# st-link-v2.net
KiCad netlist of a schematic drawn in Altium Designer
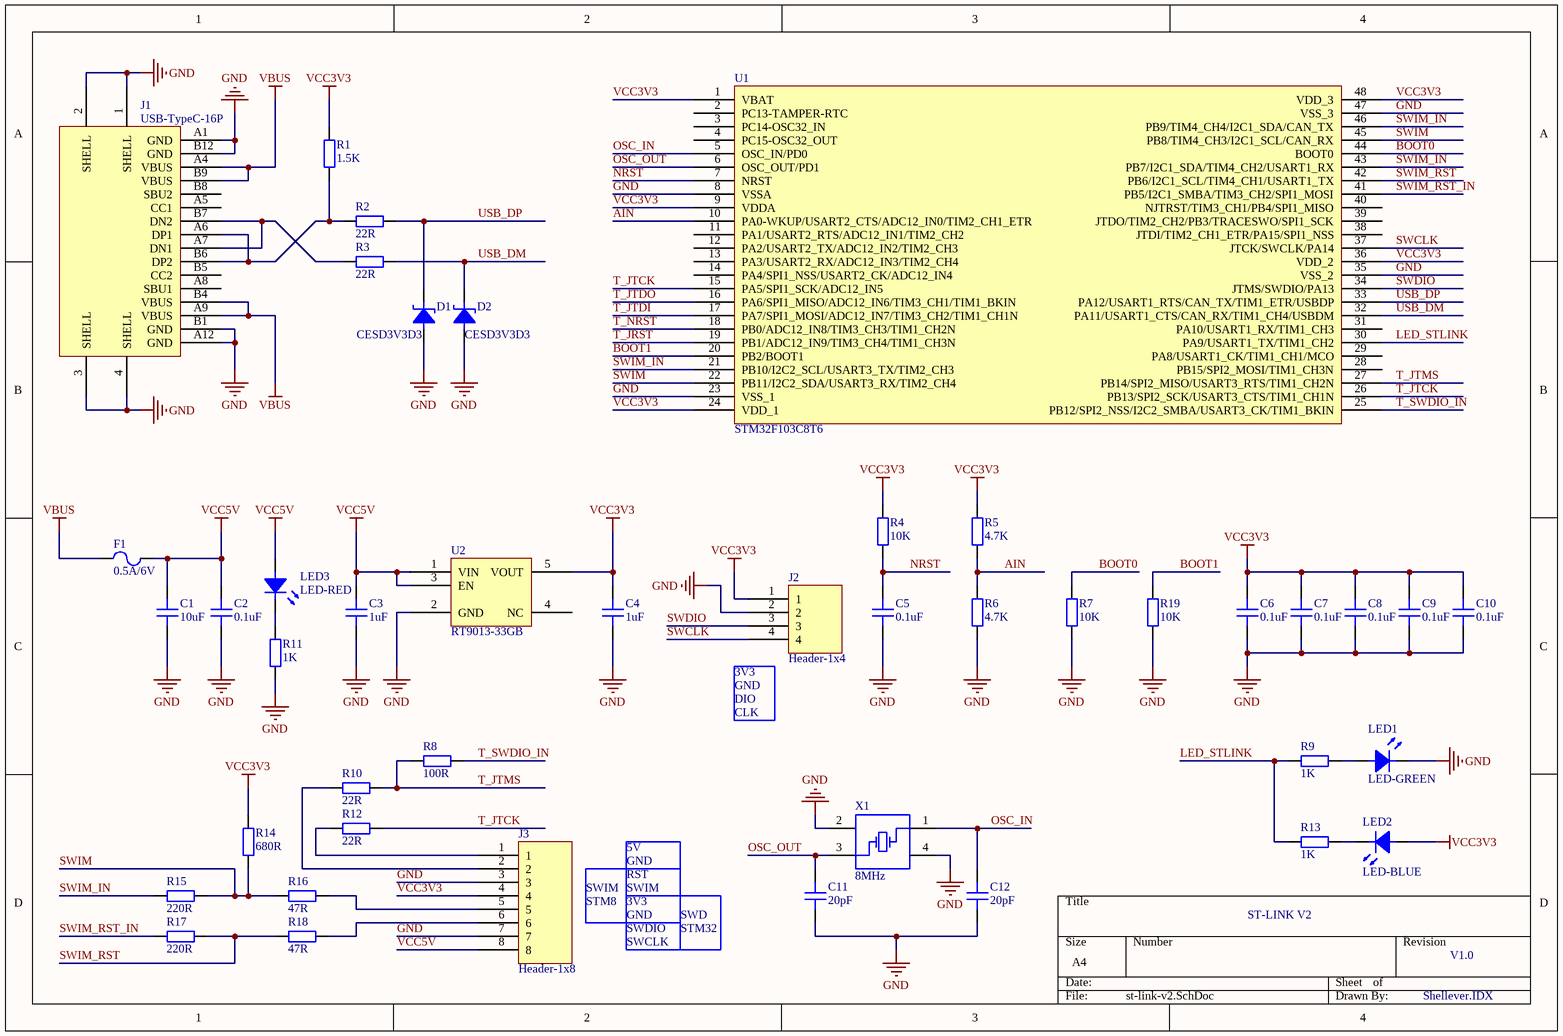
[diagram p0: st-link-v2.SchDoc]

(export (version "E")
  (design (tool "Eeschema 10.0.6"))
  (components
    (comp (ref "C1")
      (value "10uF")
      (footprint "0603C")
      (description "Capacitor")
      (libsource (lib "LinuxforSchLib") (part "CAP"))
    )
    (comp (ref "C2")
      (value "0.1uF")
      (footprint "0603C")
      (description "Capacitor")
      (libsource (lib "LinuxforSchLib") (part "CAP"))
    )
    (comp (ref "C3")
      (value "1uF")
      (footprint "0603C")
      (description "Capacitor")
      (libsource (lib "LinuxforSchLib") (part "CAP"))
    )
    (comp (ref "C4")
      (value "1uF")
      (footprint "0603C")
      (description "Capacitor")
      (libsource (lib "LinuxforSchLib") (part "CAP"))
    )
    (comp (ref "C5")
      (value "0.1uF")
      (footprint "0603C")
      (description "Capacitor")
      (libsource (lib "LinuxforSchLib") (part "CAP"))
    )
    (comp (ref "C6")
      (value "0.1uF")
      (footprint "0603C")
      (description "Capacitor")
      (libsource (lib "LinuxforSchLib") (part "CAP"))
    )
    (comp (ref "C7")
      (value "0.1uF")
      (footprint "0603C")
      (description "Capacitor")
      (libsource (lib "LinuxforSchLib") (part "CAP"))
    )
    (comp (ref "C8")
      (value "0.1uF")
      (footprint "0603C")
      (description "Capacitor")
      (libsource (lib "LinuxforSchLib") (part "CAP"))
    )
    (comp (ref "C9")
      (value "0.1uF")
      (footprint "0603C")
      (description "Capacitor")
      (libsource (lib "LinuxforSchLib") (part "CAP"))
    )
    (comp (ref "C10")
      (value "0.1uF")
      (footprint "0603C")
      (description "Capacitor")
      (libsource (lib "LinuxforSchLib") (part "CAP"))
    )
    (comp (ref "C11")
      (value "20pF")
      (footprint "0603C")
      (description "Capacitor")
      (libsource (lib "LinuxforSchLib") (part "CAP"))
    )
    (comp (ref "C12")
      (value "20pF")
      (footprint "0603C")
      (description "Capacitor")
      (libsource (lib "LinuxforSchLib") (part "CAP"))
    )
    (comp (ref "D1")
      (value "CESD3V3D3")
      (footprint "SOD-323_L1.8-W1.3-LS2.5-RD")
      (description "Uni-direction ESD Protection Diode")
      (libsource (lib "LinuxforSchLib") (part "CESD3V3D3"))
    )
    (comp (ref "D2")
      (value "CESD3V3D3")
      (footprint "SOD-323_L1.8-W1.3-LS2.5-RD")
      (description "Uni-direction ESD Protection Diode")
      (libsource (lib "LinuxforSchLib") (part "CESD3V3D3"))
    )
    (comp (ref "F1")
      (value "0.5A/6V")
      (footprint "0603F")
      (description "Fuse")
      (libsource (lib "LinuxforSchLib") (part "Fuse"))
    )
    (comp (ref "J1")
      (value "USB-TypeC-16P")
      (footprint "USB-C-SMD_KH-TYPE-C-16P")
      (description "USB Type C 16 Pin Female")
      (libsource (lib "LinuxforSchLib") (part "USB-TypeC-16P"))
    )
    (comp (ref "J2")
      (value "Header-1x4")
      (footprint "HDR-TH_4P-P2.54-V-M")
      (description "Header with 1x4 pins")
      (libsource (lib "LinuxforSchLib") (part "Header-1x4"))
    )
    (comp (ref "J3")
      (value "Header-1x8")
      (footprint "HDR-TH_8P-P2.54-V-M")
      (description "Header with 1x8 pins")
      (libsource (lib "LinuxforSchLib") (part "Header-1x8"))
    )
    (comp (ref "LED1")
      (value "LED-GREEN")
      (footprint "0603LED")
      (description "LED")
      (libsource (lib "LinuxforSchLib") (part "LED"))
    )
    (comp (ref "LED2")
      (value "LED-BLUE")
      (footprint "0603LED")
      (description "LED")
      (libsource (lib "LinuxforSchLib") (part "LED"))
    )
    (comp (ref "LED3")
      (value "LED-RED")
      (footprint "0603LED")
      (description "LED")
      (libsource (lib "") (part "LED_1"))
    )
    (comp (ref "R1")
      (value "1.5K")
      (footprint "0603R")
      (description "Resistor")
      (libsource (lib "LinuxforSchLib") (part "RES"))
    )
    (comp (ref "R2")
      (value "22R")
      (footprint "0603R")
      (description "Resistor")
      (libsource (lib "LinuxforSchLib") (part "RES"))
    )
    (comp (ref "R3")
      (value "22R")
      (footprint "0603R")
      (description "Resistor")
      (libsource (lib "LinuxforSchLib") (part "RES"))
    )
    (comp (ref "R4")
      (value "10K")
      (footprint "0603R")
      (description "Resistor")
      (libsource (lib "LinuxforSchLib") (part "RES"))
    )
    (comp (ref "R5")
      (value "4.7K")
      (footprint "0603R")
      (description "Resistor")
      (libsource (lib "LinuxforSchLib") (part "RES"))
    )
    (comp (ref "R6")
      (value "4.7K")
      (footprint "0603R")
      (description "Resistor")
      (libsource (lib "LinuxforSchLib") (part "RES"))
    )
    (comp (ref "R7")
      (value "10K")
      (footprint "0603R")
      (description "Resistor")
      (libsource (lib "LinuxforSchLib") (part "RES"))
    )
    (comp (ref "R8")
      (value "100R")
      (footprint "0603R")
      (description "Resistor")
      (libsource (lib "LinuxforSchLib") (part "RES"))
    )
    (comp (ref "R9")
      (value "1K")
      (footprint "0603R")
      (description "Resistor")
      (libsource (lib "LinuxforSchLib") (part "RES"))
    )
    (comp (ref "R10")
      (value "22R")
      (footprint "0603R")
      (description "Resistor")
      (libsource (lib "LinuxforSchLib") (part "RES"))
    )
    (comp (ref "R11")
      (value "1K")
      (footprint "0603R")
      (description "Resistor")
      (libsource (lib "LinuxforSchLib") (part "RES"))
    )
    (comp (ref "R12")
      (value "22R")
      (footprint "0603R")
      (description "Resistor")
      (libsource (lib "LinuxforSchLib") (part "RES"))
    )
    (comp (ref "R13")
      (value "1K")
      (footprint "0603R")
      (description "Resistor")
      (libsource (lib "LinuxforSchLib") (part "RES"))
    )
    (comp (ref "R14")
      (value "680R")
      (footprint "0603R")
      (description "Resistor")
      (libsource (lib "LinuxforSchLib") (part "RES"))
    )
    (comp (ref "R15")
      (value "220R")
      (footprint "0603R")
      (description "Resistor")
      (libsource (lib "LinuxforSchLib") (part "RES"))
    )
    (comp (ref "R16")
      (value "47R")
      (footprint "0603R")
      (description "Resistor")
      (libsource (lib "LinuxforSchLib") (part "RES"))
    )
    (comp (ref "R17")
      (value "220R")
      (footprint "0603R")
      (description "Resistor")
      (libsource (lib "LinuxforSchLib") (part "RES"))
    )
    (comp (ref "R18")
      (value "47R")
      (footprint "0603R")
      (description "Resistor")
      (libsource (lib "LinuxforSchLib") (part "RES"))
    )
    (comp (ref "R19")
      (value "10K")
      (footprint "0603R")
      (description "Resistor")
      (libsource (lib "LinuxforSchLib") (part "RES"))
    )
    (comp (ref "U1")
      (value "STM32F103C8T6")
      (footprint "LQFP-48_L7.0-W7.0-P0.50-LS9.0-BL")
      (description "STM32F103x8 LQFP48")
      (libsource (lib "LinuxforSchLib") (part "STM32F103x8_LQFP48"))
    )
    (comp (ref "U2")
      (value "RT9013-33GB")
      (footprint "SOT-23-5_L3.0-W1.7-P0.95-LS2.8-BR")
      (description "500mA LDO Regulator without Bypass Capacitor")
      (fields
        (field (name "MANUFACTURER") "RICHTEK<https://tw.richtek.com/>")
        (field (name "CONTRIBUTOR") "Shellever.IDX<shellever@163.com>")
      )
      (libsource (lib "LinuxforSchLib") (part "RT9013"))
    )
    (comp (ref "X1")
      (value "8MHz")
      (footprint "OSC-SMD_3225-4P-L3.2-W2.5-BL")
      (description "passive crystal 8MHz")
      (libsource (lib "LinuxforSchLib") (part "XTAL-Crystal-MHz"))
    )
  )
  (nets
    (net (code "1") (name "/AIN") (class "Default")
      (node (ref "R5") (pin "1") (pinfunction "1_1") (pintype "passive"))
      (node (ref "R6") (pin "2") (pinfunction "2_2") (pintype "passive"))
      (node (ref "U1") (pin "10") (pinfunction "PA0-WKUP/USART2_CTS/ADC12_IN0/TIM2_CH1_ETR_10") (pintype "passive"))
    )
    (net (code "2") (name "/BOOT0") (class "Default")
      (node (ref "R7") (pin "2") (pinfunction "2_2") (pintype "passive"))
      (node (ref "U1") (pin "44") (pinfunction "BOOT0_44") (pintype "passive"))
    )
    (net (code "3") (name "/BOOT1") (class "Default")
      (node (ref "R19") (pin "2") (pinfunction "2_2") (pintype "passive"))
      (node (ref "U1") (pin "20") (pinfunction "PB2/BOOT1_20") (pintype "passive"))
    )
    (net (code "4") (name "/LED_STLINK") (class "Default")
      (node (ref "R13") (pin "2") (pinfunction "2_2") (pintype "passive"))
      (node (ref "R9") (pin "2") (pinfunction "2_2") (pintype "passive"))
      (node (ref "U1") (pin "30") (pinfunction "PA9/USART1_TX/TIM1_CH2_30") (pintype "passive"))
    )
    (net (code "5") (name "/NRST") (class "Default")
      (node (ref "C5") (pin "2") (pinfunction "2_2") (pintype "passive"))
      (node (ref "R4") (pin "1") (pinfunction "1_1") (pintype "passive"))
      (node (ref "U1") (pin "7") (pinfunction "NRST_7") (pintype "passive"))
    )
    (net (code "6") (name "/OSC_IN") (class "Default")
      (node (ref "C12") (pin "2") (pinfunction "2_2") (pintype "passive"))
      (node (ref "U1") (pin "5") (pinfunction "OSC_IN/PD0_5") (pintype "passive"))
      (node (ref "X1") (pin "1") (pinfunction "OSC1_1") (pintype "passive"))
    )
    (net (code "7") (name "/OSC_OUT") (class "Default")
      (node (ref "C11") (pin "1") (pinfunction "1_1") (pintype "passive"))
      (node (ref "U1") (pin "6") (pinfunction "OSC_OUT/PD1_6") (pintype "passive"))
      (node (ref "X1") (pin "3") (pinfunction "OSC2_3") (pintype "passive"))
    )
    (net (code "8") (name "/SWCLK") (class "Default")
      (node (ref "J2") (pin "4") (pinfunction "4_4") (pintype "passive"))
      (node (ref "U1") (pin "37") (pinfunction "JTCK/SWCLK/PA14_37") (pintype "passive"))
    )
    (net (code "9") (name "/SWDIO") (class "Default")
      (node (ref "J2") (pin "3") (pinfunction "3_3") (pintype "passive"))
      (node (ref "U1") (pin "34") (pinfunction "JTMS/SWDIO/PA13_34") (pintype "passive"))
    )
    (net (code "10") (name "/SWIM") (class "Default")
      (node (ref "R14") (pin "1") (pinfunction "1_1") (pintype "passive"))
      (node (ref "R15") (pin "1") (pinfunction "1_1") (pintype "passive"))
      (node (ref "R16") (pin "2") (pinfunction "2_2") (pintype "passive"))
      (node (ref "U1") (pin "22") (pinfunction "PB11/I2C2_SDA/USART3_RX/TIM2_CH4_22") (pintype "passive"))
      (node (ref "U1") (pin "45") (pinfunction "PB8/TIM4_CH3/I2C1_SCL/CAN_RX_45") (pintype "passive"))
    )
    (net (code "11") (name "/SWIM_IN") (class "Default")
      (node (ref "R15") (pin "2") (pinfunction "2_2") (pintype "passive"))
      (node (ref "U1") (pin "21") (pinfunction "PB10/I2C2_SCL/USART3_TX/TIM2_CH3_21") (pintype "passive"))
      (node (ref "U1") (pin "43") (pinfunction "PB7/I2C1_SDA/TIM4_CH2/USART1_RX_43") (pintype "passive"))
      (node (ref "U1") (pin "46") (pinfunction "PB9/TIM4_CH4/I2C1_SDA/CAN_TX_46") (pintype "passive"))
    )
    (net (code "12") (name "/SWIM_RST") (class "Default")
      (node (ref "R17") (pin "1") (pinfunction "1_1") (pintype "passive"))
      (node (ref "R18") (pin "2") (pinfunction "2_2") (pintype "passive"))
      (node (ref "U1") (pin "42") (pinfunction "PB6/I2C1_SCL/TIM4_CH1/USART1_TX_42") (pintype "passive"))
    )
    (net (code "13") (name "/SWIM_RST_IN") (class "Default")
      (node (ref "R17") (pin "2") (pinfunction "2_2") (pintype "passive"))
      (node (ref "U1") (pin "41") (pinfunction "PB5/I2C1_SMBA/TIM3_CH2/SPI1_MOSI_41") (pintype "passive"))
    )
    (net (code "14") (name "/T_JRST") (class "Default")
      (node (ref "U1") (pin "19") (pinfunction "PB1/ADC12_IN9/TIM3_CH4/TIM1_CH3N_19") (pintype "passive"))
    )
    (net (code "15") (name "/T_JTCK") (class "Default")
      (node (ref "R12") (pin "1") (pinfunction "1_1") (pintype "passive"))
      (node (ref "U1") (pin "15") (pinfunction "PA5/SPI1_SCK/ADC12_IN5_15") (pintype "passive"))
      (node (ref "U1") (pin "26") (pinfunction "PB13/SPI2_SCK/USART3_CTS/TIM1_CH1N_26") (pintype "passive"))
    )
    (net (code "16") (name "/T_JTDI") (class "Default")
      (node (ref "U1") (pin "17") (pinfunction "PA7/SPI1_MOSI/ADC12_IN7/TIM3_CH2/TIM1_CH1N_17") (pintype "passive"))
    )
    (net (code "17") (name "/T_JTDO") (class "Default")
      (node (ref "U1") (pin "16") (pinfunction "PA6/SPI1_MISO/ADC12_IN6/TIM3_CH1/TIM1_BKIN_16") (pintype "passive"))
    )
    (net (code "18") (name "/T_JTMS") (class "Default")
      (node (ref "R10") (pin "1") (pinfunction "1_1") (pintype "passive"))
      (node (ref "R8") (pin "2") (pinfunction "2_2") (pintype "passive"))
      (node (ref "U1") (pin "27") (pinfunction "PB14/SPI2_MISO/USART3_RTS/TIM1_CH2N_27") (pintype "passive"))
    )
    (net (code "19") (name "/T_NRST") (class "Default")
      (node (ref "U1") (pin "18") (pinfunction "PB0/ADC12_IN8/TIM3_CH3/TIM1_CH2N_18") (pintype "passive"))
    )
    (net (code "20") (name "/T_SWDIO_IN") (class "Default")
      (node (ref "R8") (pin "1") (pinfunction "1_1") (pintype "passive"))
      (node (ref "U1") (pin "25") (pinfunction "PB12/SPI2_NSS/I2C2_SMBA/USART3_CK/TIM1_BKIN_25") (pintype "passive"))
    )
    (net (code "21") (name "/USB_DM") (class "Default")
      (node (ref "D2") (pin "1") (pinfunction "K_1") (pintype "passive"))
      (node (ref "R3") (pin "2") (pinfunction "2_2") (pintype "passive"))
      (node (ref "U1") (pin "32") (pinfunction "PA11/USART1_CTS/CAN_RX/TIM1_CH4/USBDM_32") (pintype "passive"))
    )
    (net (code "22") (name "/USB_DP") (class "Default")
      (node (ref "D1") (pin "1") (pinfunction "K_1") (pintype "passive"))
      (node (ref "R2") (pin "2") (pinfunction "2_2") (pintype "passive"))
      (node (ref "U1") (pin "33") (pinfunction "PA12/USART1_RTS/CAN_TX/TIM1_ETR/USBDP_33") (pintype "passive"))
    )
    (net (code "23") (name "GND") (class "Default")
      (node (ref "C1") (pin "1") (pinfunction "1_1") (pintype "passive"))
      (node (ref "C10") (pin "1") (pinfunction "1_1") (pintype "passive"))
      (node (ref "C11") (pin "2") (pinfunction "2_2") (pintype "passive"))
      (node (ref "C12") (pin "1") (pinfunction "1_1") (pintype "passive"))
      (node (ref "C2") (pin "1") (pinfunction "1_1") (pintype "passive"))
      (node (ref "C3") (pin "1") (pinfunction "1_1") (pintype "passive"))
      (node (ref "C4") (pin "1") (pinfunction "1_1") (pintype "passive"))
      (node (ref "C5") (pin "1") (pinfunction "1_1") (pintype "passive"))
      (node (ref "C6") (pin "1") (pinfunction "1_1") (pintype "passive"))
      (node (ref "C7") (pin "1") (pinfunction "1_1") (pintype "passive"))
      (node (ref "C8") (pin "1") (pinfunction "1_1") (pintype "passive"))
      (node (ref "C9") (pin "1") (pinfunction "1_1") (pintype "passive"))
      (node (ref "D1") (pin "2") (pinfunction "A_2") (pintype "passive"))
      (node (ref "D2") (pin "2") (pinfunction "A_2") (pintype "passive"))
      (node (ref "J1") (pin "1") (pinfunction "SHELL_1") (pintype "passive"))
      (node (ref "J1") (pin "2") (pinfunction "SHELL_2") (pintype "passive"))
      (node (ref "J1") (pin "3") (pinfunction "SHELL_3") (pintype "passive"))
      (node (ref "J1") (pin "4") (pinfunction "SHELL_4") (pintype "passive"))
      (node (ref "J1") (pin "A1") (pinfunction "GND_A1") (pintype "passive"))
      (node (ref "J1") (pin "A12") (pinfunction "GND_A12") (pintype "passive"))
      (node (ref "J1") (pin "B1") (pinfunction "GND_B1") (pintype "passive"))
      (node (ref "J1") (pin "B12") (pinfunction "GND_B12") (pintype "passive"))
      (node (ref "J2") (pin "2") (pinfunction "2_2") (pintype "passive"))
      (node (ref "J3") (pin "3") (pinfunction "3_3") (pintype "passive"))
      (node (ref "J3") (pin "7") (pinfunction "7_7") (pintype "passive"))
      (node (ref "LED1") (pin "2") (pinfunction "K_2") (pintype "passive"))
      (node (ref "R11") (pin "1") (pinfunction "1_1") (pintype "passive"))
      (node (ref "R19") (pin "1") (pinfunction "1_1") (pintype "passive"))
      (node (ref "R6") (pin "1") (pinfunction "1_1") (pintype "passive"))
      (node (ref "R7") (pin "1") (pinfunction "1_1") (pintype "passive"))
      (node (ref "U1") (pin "23") (pinfunction "VSS_1_23") (pintype "passive"))
      (node (ref "U1") (pin "35") (pinfunction "VSS_2_35") (pintype "passive"))
      (node (ref "U1") (pin "47") (pinfunction "VSS_3_47") (pintype "passive"))
      (node (ref "U1") (pin "8") (pinfunction "VSSA_8") (pintype "passive"))
      (node (ref "U2") (pin "2") (pinfunction "GND_2") (pintype "passive"))
      (node (ref "X1") (pin "2") (pinfunction "GND_2") (pintype "passive"))
      (node (ref "X1") (pin "4") (pinfunction "GND_4") (pintype "passive"))
    )
    (net (code "24") (name "Net-(J1-DN1)") (class "Default")
      (node (ref "J1") (pin "A7") (pinfunction "DN1_A7") (pintype "passive"))
      (node (ref "J1") (pin "B7") (pinfunction "DN2_B7") (pintype "passive"))
      (node (ref "R3") (pin "1") (pinfunction "1_1") (pintype "passive"))
    )
    (net (code "25") (name "Net-(J1-DP1)") (class "Default")
      (node (ref "J1") (pin "A6") (pinfunction "DP1_A6") (pintype "passive"))
      (node (ref "J1") (pin "B6") (pinfunction "DP2_B6") (pintype "passive"))
      (node (ref "R1") (pin "1") (pinfunction "1_1") (pintype "passive"))
      (node (ref "R2") (pin "1") (pinfunction "1_1") (pintype "passive"))
    )
    (net (code "26") (name "Net-(J3-Pad1)") (class "Default")
      (node (ref "J3") (pin "1") (pinfunction "1_1") (pintype "passive"))
      (node (ref "R12") (pin "2") (pinfunction "2_2") (pintype "passive"))
    )
    (net (code "27") (name "Net-(J3-Pad2)") (class "Default")
      (node (ref "J3") (pin "2") (pinfunction "2_2") (pintype "passive"))
      (node (ref "R10") (pin "2") (pinfunction "2_2") (pintype "passive"))
    )
    (net (code "28") (name "Net-(J3-Pad5)") (class "Default")
      (node (ref "J3") (pin "5") (pinfunction "5_5") (pintype "passive"))
      (node (ref "R16") (pin "1") (pinfunction "1_1") (pintype "passive"))
    )
    (net (code "29") (name "Net-(J3-Pad6)") (class "Default")
      (node (ref "J3") (pin "6") (pinfunction "6_6") (pintype "passive"))
      (node (ref "R18") (pin "1") (pinfunction "1_1") (pintype "passive"))
    )
    (net (code "30") (name "Net-(LED1-A)") (class "Default")
      (node (ref "LED1") (pin "1") (pinfunction "A_1") (pintype "passive"))
      (node (ref "R9") (pin "1") (pinfunction "1_1") (pintype "passive"))
    )
    (net (code "31") (name "Net-(LED2-K)") (class "Default")
      (node (ref "LED2") (pin "2") (pinfunction "K_2") (pintype "passive"))
      (node (ref "R13") (pin "1") (pinfunction "1_1") (pintype "passive"))
    )
    (net (code "32") (name "Net-(LED3-K)") (class "Default")
      (node (ref "LED3") (pin "2") (pinfunction "K_2") (pintype "passive"))
      (node (ref "R11") (pin "2") (pinfunction "2_2") (pintype "passive"))
    )
    (net (code "33") (name "VBUS") (class "Default")
      (node (ref "F1") (pin "1") (pinfunction "1_1") (pintype "passive"))
      (node (ref "J1") (pin "A4") (pinfunction "VBUS_A4") (pintype "passive"))
      (node (ref "J1") (pin "A9") (pinfunction "VBUS_A9") (pintype "passive"))
      (node (ref "J1") (pin "B4") (pinfunction "VBUS_B4") (pintype "passive"))
      (node (ref "J1") (pin "B9") (pinfunction "VBUS_B9") (pintype "passive"))
    )
    (net (code "34") (name "VCC3V3") (class "Default")
      (node (ref "C10") (pin "2") (pinfunction "2_2") (pintype "passive"))
      (node (ref "C4") (pin "2") (pinfunction "2_2") (pintype "passive"))
      (node (ref "C6") (pin "2") (pinfunction "2_2") (pintype "passive"))
      (node (ref "C7") (pin "2") (pinfunction "2_2") (pintype "passive"))
      (node (ref "C8") (pin "2") (pinfunction "2_2") (pintype "passive"))
      (node (ref "C9") (pin "2") (pinfunction "2_2") (pintype "passive"))
      (node (ref "J2") (pin "1") (pinfunction "1_1") (pintype "passive"))
      (node (ref "J3") (pin "4") (pinfunction "4_4") (pintype "passive"))
      (node (ref "LED2") (pin "1") (pinfunction "A_1") (pintype "passive"))
      (node (ref "R1") (pin "2") (pinfunction "2_2") (pintype "passive"))
      (node (ref "R14") (pin "2") (pinfunction "2_2") (pintype "passive"))
      (node (ref "R4") (pin "2") (pinfunction "2_2") (pintype "passive"))
      (node (ref "R5") (pin "2") (pinfunction "2_2") (pintype "passive"))
      (node (ref "U1") (pin "1") (pinfunction "VBAT_1") (pintype "passive"))
      (node (ref "U1") (pin "24") (pinfunction "VDD_1_24") (pintype "passive"))
      (node (ref "U1") (pin "36") (pinfunction "VDD_2_36") (pintype "passive"))
      (node (ref "U1") (pin "48") (pinfunction "VDD_3_48") (pintype "passive"))
      (node (ref "U1") (pin "9") (pinfunction "VDDA_9") (pintype "passive"))
      (node (ref "U2") (pin "5") (pinfunction "VOUT_5") (pintype "passive"))
    )
    (net (code "35") (name "VCC5V") (class "Default")
      (node (ref "C1") (pin "2") (pinfunction "2_2") (pintype "passive"))
      (node (ref "C2") (pin "2") (pinfunction "2_2") (pintype "passive"))
      (node (ref "C3") (pin "2") (pinfunction "2_2") (pintype "passive"))
      (node (ref "F1") (pin "2") (pinfunction "2_2") (pintype "passive"))
      (node (ref "J3") (pin "8") (pinfunction "8_8") (pintype "passive"))
      (node (ref "LED3") (pin "1") (pinfunction "A_1") (pintype "passive"))
      (node (ref "U2") (pin "1") (pinfunction "VIN_1") (pintype "passive"))
      (node (ref "U2") (pin "3") (pinfunction "EN_3") (pintype "passive"))
    )
    (net (code "36") (name "unconnected-(J1-CC1-PadA5)") (class "Default")
      (node (ref "J1") (pin "A5") (pinfunction "CC1_A5") (pintype "passive"))
    )
    (net (code "37") (name "unconnected-(J1-CC2-PadB5)") (class "Default")
      (node (ref "J1") (pin "B5") (pinfunction "CC2_B5") (pintype "passive"))
    )
    (net (code "38") (name "unconnected-(J1-SBU1-PadA8)") (class "Default")
      (node (ref "J1") (pin "A8") (pinfunction "SBU1_A8") (pintype "passive"))
    )
    (net (code "39") (name "unconnected-(J1-SBU2-PadB8)") (class "Default")
      (node (ref "J1") (pin "B8") (pinfunction "SBU2_B8") (pintype "passive"))
    )
    (net (code "40") (name "unconnected-(U1-JTDI{slash}TIM2_CH1_ETR{slash}PA15{slash}SPI1_NSS-Pad38)") (class "Default")
      (node (ref "U1") (pin "38") (pinfunction "JTDI/TIM2_CH1_ETR/PA15/SPI1_NSS_38") (pintype "passive"))
    )
    (net (code "41") (name "unconnected-(U1-JTDO{slash}TIM2_CH2{slash}PB3{slash}TRACESWO{slash}SPI1_SCK-Pad39)") (class "Default")
      (node (ref "U1") (pin "39") (pinfunction "JTDO/TIM2_CH2/PB3/TRACESWO/SPI1_SCK_39") (pintype "passive"))
    )
    (net (code "42") (name "unconnected-(U1-NJTRST{slash}TIM3_CH1{slash}PB4{slash}SPI1_MISO-Pad40)") (class "Default")
      (node (ref "U1") (pin "40") (pinfunction "NJTRST/TIM3_CH1/PB4/SPI1_MISO_40") (pintype "passive"))
    )
    (net (code "43") (name "unconnected-(U1-PA1{slash}USART2_RTS{slash}ADC12_IN1{slash}TIM2_CH2-Pad11)") (class "Default")
      (node (ref "U1") (pin "11") (pinfunction "PA1/USART2_RTS/ADC12_IN1/TIM2_CH2_11") (pintype "passive"))
    )
    (net (code "44") (name "unconnected-(U1-PA2{slash}USART2_TX{slash}ADC12_IN2{slash}TIM2_CH3-Pad12)") (class "Default")
      (node (ref "U1") (pin "12") (pinfunction "PA2/USART2_TX/ADC12_IN2/TIM2_CH3_12") (pintype "passive"))
    )
    (net (code "45") (name "unconnected-(U1-PA3{slash}USART2_RX{slash}ADC12_IN3{slash}TIM2_CH4-Pad13)") (class "Default")
      (node (ref "U1") (pin "13") (pinfunction "PA3/USART2_RX/ADC12_IN3/TIM2_CH4_13") (pintype "passive"))
    )
    (net (code "46") (name "unconnected-(U1-PA4{slash}SPI1_NSS{slash}USART2_CK{slash}ADC12_IN4-Pad14)") (class "Default")
      (node (ref "U1") (pin "14") (pinfunction "PA4/SPI1_NSS/USART2_CK/ADC12_IN4_14") (pintype "passive"))
    )
    (net (code "47") (name "unconnected-(U1-PA8{slash}USART1_CK{slash}TIM1_CH1{slash}MCO-Pad29)") (class "Default")
      (node (ref "U1") (pin "29") (pinfunction "PA8/USART1_CK/TIM1_CH1/MCO_29") (pintype "passive"))
    )
    (net (code "48") (name "unconnected-(U1-PA10{slash}USART1_RX{slash}TIM1_CH3-Pad31)") (class "Default")
      (node (ref "U1") (pin "31") (pinfunction "PA10/USART1_RX/TIM1_CH3_31") (pintype "passive"))
    )
    (net (code "49") (name "unconnected-(U1-PB15{slash}SPI2_MOSI{slash}TIM1_CH3N-Pad28)") (class "Default")
      (node (ref "U1") (pin "28") (pinfunction "PB15/SPI2_MOSI/TIM1_CH3N_28") (pintype "passive"))
    )
    (net (code "50") (name "unconnected-(U1-PC13-TAMPER-RTC-Pad2)") (class "Default")
      (node (ref "U1") (pin "2") (pinfunction "PC13-TAMPER-RTC_2") (pintype "passive"))
    )
    (net (code "51") (name "unconnected-(U1-PC14-OSC32_IN-Pad3)") (class "Default")
      (node (ref "U1") (pin "3") (pinfunction "PC14-OSC32_IN_3") (pintype "passive"))
    )
    (net (code "52") (name "unconnected-(U1-PC15-OSC32_OUT-Pad4)") (class "Default")
      (node (ref "U1") (pin "4") (pinfunction "PC15-OSC32_OUT_4") (pintype "passive"))
    )
    (net (code "53") (name "unconnected-(U2-NC-Pad4)") (class "Default")
      (node (ref "U2") (pin "4") (pinfunction "NC_4") (pintype "passive"))
    )
  )
)
